# appleii.net
KiCad netlist of a schematic drawn in EAGLE
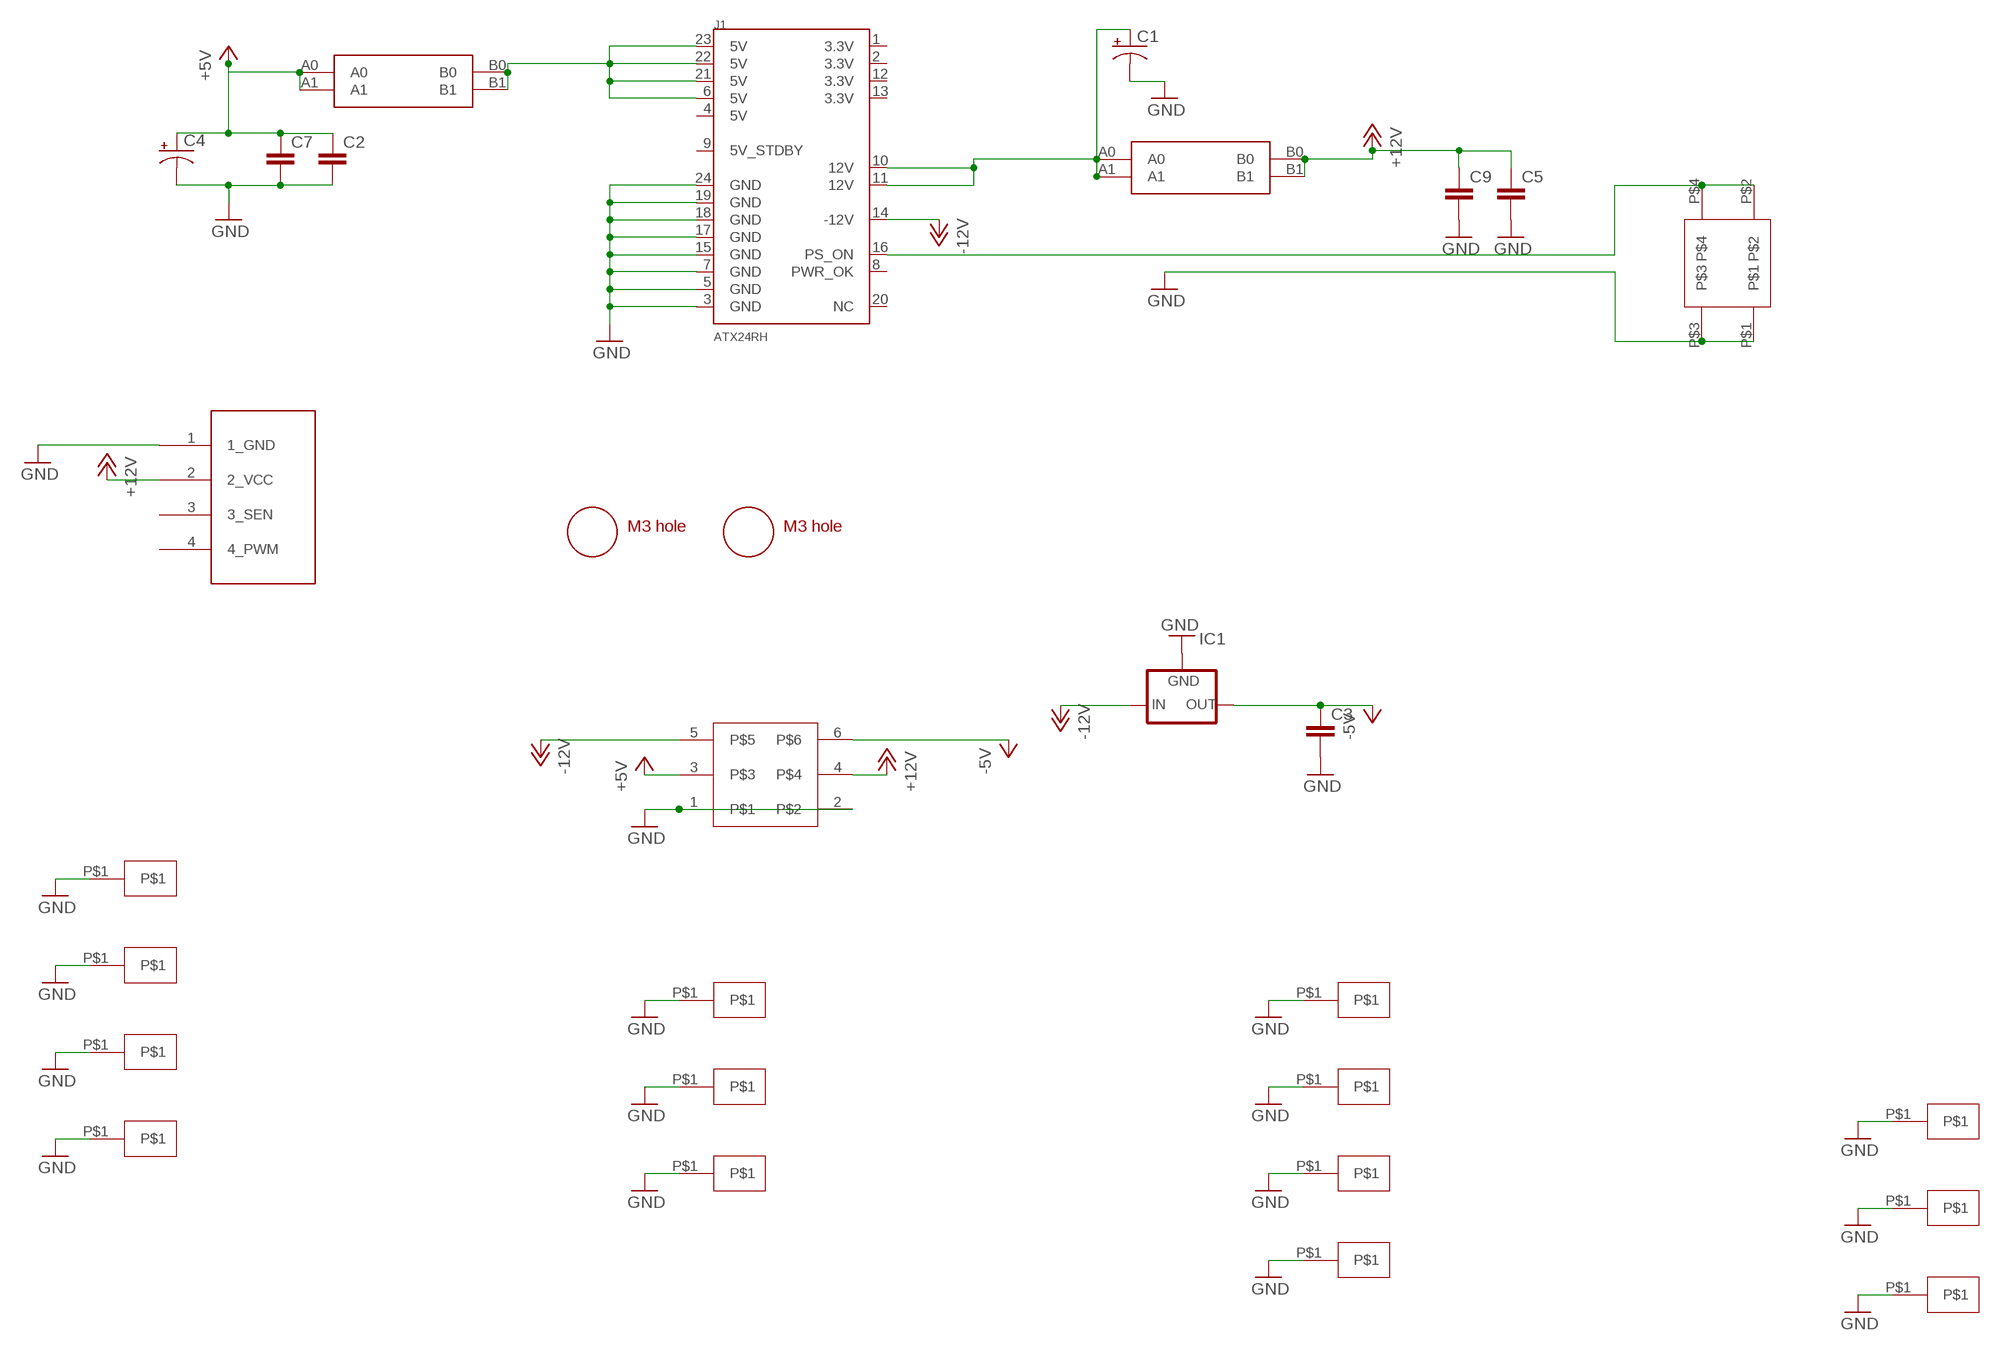
[diagram p0: schematic, sheet 1]

(export (version "E")
  (design (tool "Eeschema 10.0.6"))
  (components
    (comp (ref "C1")
      (value "CPOL-USE3.5-8")
      (footprint "eagle-import:E3,5-8")
      (libsource (lib "eagle-import") (part "CPOL-USE3.5-8"))
    )
    (comp (ref "C2")
      (value "C5/2.5")
      (footprint "eagle-import:C5B2.5")
      (libsource (lib "eagle-import") (part "C5/2.5"))
    )
    (comp (ref "C3")
      (value "C5/2.5")
      (footprint "eagle-import:C5B2.5")
      (libsource (lib "eagle-import") (part "C5/2.5"))
    )
    (comp (ref "C4")
      (value "CPOL-USE3.5-8")
      (footprint "eagle-import:E3,5-8")
      (libsource (lib "eagle-import") (part "CPOL-USE3.5-8"))
    )
    (comp (ref "C5")
      (value "C5/2.5")
      (footprint "eagle-import:C5B2.5")
      (libsource (lib "eagle-import") (part "C5/2.5"))
    )
    (comp (ref "C7")
      (value "C5/2.5")
      (footprint "eagle-import:C5B2.5")
      (libsource (lib "eagle-import") (part "C5/2.5"))
    )
    (comp (ref "C9")
      (value "C5/2.5")
      (footprint "eagle-import:C5B2.5")
      (libsource (lib "eagle-import") (part "C5/2.5"))
    )
    (comp (ref "IC1")
      (value "79XXS")
      (footprint "eagle-import:79XXS")
      (libsource (lib "eagle-import") (part "79XXS"))
    )
    (comp (ref "J1")
      (value "ATX24RH")
      (footprint "eagle-import:ATX24_RIGHT_ANGLE")
      (libsource (lib "eagle-import") (part "ATX24RH"))
    )
    (comp (ref "JP3")
      (value "4PIN_FAN")
      (footprint "eagle-import:1X04")
      (libsource (lib "eagle-import") (part "4PIN_FAN"))
    )
    (comp (ref "U$1")
      (value "CAR_FUSE_HOLDER3IN1")
      (footprint "eagle-import:FUSE_HOLDER_3IN1")
      (libsource (lib "eagle-import") (part "CAR_FUSE_HOLDER3IN1"))
    )
    (comp (ref "U$2")
      (value "CAR_FUSE_HOLDER3IN1")
      (footprint "eagle-import:FUSE_HOLDER_3IN1")
      (libsource (lib "eagle-import") (part "CAR_FUSE_HOLDER3IN1"))
    )
    (comp (ref "U$3")
      (value "ROCK_SW")
      (footprint "eagle-import:ROCK_SWITCH")
      (libsource (lib "eagle-import") (part "ROCK_SW"))
    )
    (comp (ref "U$4")
      (value "M3_MOUNTING_HOLE")
      (footprint "eagle-import:M3_MOUNTING_HOLE_PACK")
      (libsource (lib "eagle-import") (part "M3_MOUNTING_HOLE"))
    )
    (comp (ref "U$5")
      (value "M3_MOUNTING_HOLE")
      (footprint "eagle-import:M3_MOUNTING_HOLE_PACK")
      (libsource (lib "eagle-import") (part "M3_MOUNTING_HOLE"))
    )
    (comp (ref "U$6")
      (value "APPLEII")
      (footprint "eagle-import:APPLEII")
      (libsource (lib "eagle-import") (part "APPLEII"))
    )
    (comp (ref "U$7")
      (value "EDGEPAD")
      (footprint "eagle-import:EDGEPAD")
      (libsource (lib "eagle-import") (part "EDGEPAD"))
    )
    (comp (ref "U$8")
      (value "EDGEPAD")
      (footprint "eagle-import:EDGEPAD")
      (libsource (lib "eagle-import") (part "EDGEPAD"))
    )
    (comp (ref "U$9")
      (value "EDGEPAD")
      (footprint "eagle-import:EDGEPAD")
      (libsource (lib "eagle-import") (part "EDGEPAD"))
    )
    (comp (ref "U$10")
      (value "EDGEPAD")
      (footprint "eagle-import:EDGEPAD")
      (libsource (lib "eagle-import") (part "EDGEPAD"))
    )
    (comp (ref "U$11")
      (value "EDGEPAD")
      (footprint "eagle-import:EDGEPAD")
      (libsource (lib "eagle-import") (part "EDGEPAD"))
    )
    (comp (ref "U$12")
      (value "EDGEPAD")
      (footprint "eagle-import:EDGEPAD")
      (libsource (lib "eagle-import") (part "EDGEPAD"))
    )
    (comp (ref "U$13")
      (value "EDGEPAD")
      (footprint "eagle-import:EDGEPAD")
      (libsource (lib "eagle-import") (part "EDGEPAD"))
    )
    (comp (ref "U$14")
      (value "EDGEPAD")
      (footprint "eagle-import:EDGEPAD")
      (libsource (lib "eagle-import") (part "EDGEPAD"))
    )
    (comp (ref "U$15")
      (value "EDGEPAD")
      (footprint "eagle-import:EDGEPAD")
      (libsource (lib "eagle-import") (part "EDGEPAD"))
    )
    (comp (ref "U$16")
      (value "EDGEPAD")
      (footprint "eagle-import:EDGEPAD")
      (libsource (lib "eagle-import") (part "EDGEPAD"))
    )
    (comp (ref "U$17")
      (value "EDGEPAD")
      (footprint "eagle-import:EDGEPAD")
      (libsource (lib "eagle-import") (part "EDGEPAD"))
    )
    (comp (ref "U$18")
      (value "EDGEPAD")
      (footprint "eagle-import:EDGEPAD")
      (libsource (lib "eagle-import") (part "EDGEPAD"))
    )
    (comp (ref "U$19")
      (value "EDGEPAD")
      (footprint "eagle-import:EDGEPAD")
      (libsource (lib "eagle-import") (part "EDGEPAD"))
    )
    (comp (ref "U$20")
      (value "EDGEPAD")
      (footprint "eagle-import:EDGEPAD")
      (libsource (lib "eagle-import") (part "EDGEPAD"))
    )
  )
  (nets
    (net (code "1") (name "+5V") (class "Default")
      (node (ref "C2") (pin "1") (pinfunction "1_1") (pintype "passive"))
      (node (ref "C4") (pin "+") (pinfunction "+_+") (pintype "passive"))
      (node (ref "C7") (pin "1") (pinfunction "1_1") (pintype "passive"))
      (node (ref "U$1") (pin "A0") (pinfunction "A0_A0") (pintype "bidirectional"))
      (node (ref "U$1") (pin "A1") (pinfunction "A1_A1") (pintype "bidirectional"))
      (node (ref "U$6") (pin "3") (pinfunction "P$3_3") (pintype "bidirectional"))
    )
    (net (code "2") (name "+12V") (class "Default")
      (node (ref "C5") (pin "1") (pinfunction "1_1") (pintype "passive"))
      (node (ref "C9") (pin "1") (pinfunction "1_1") (pintype "passive"))
      (node (ref "JP3") (pin "2") (pinfunction "2_VCC_2") (pintype "passive"))
      (node (ref "U$2") (pin "B0") (pinfunction "B0_B0") (pintype "bidirectional"))
      (node (ref "U$2") (pin "B1") (pinfunction "B1_B1") (pintype "bidirectional"))
      (node (ref "U$6") (pin "4") (pinfunction "P$4_4") (pintype "bidirectional"))
    )
    (net (code "3") (name "-5V") (class "Default")
      (node (ref "C3") (pin "1") (pinfunction "1_1") (pintype "passive"))
      (node (ref "IC1") (pin "OUT") (pinfunction "OUT_OUT") (pintype "passive"))
      (node (ref "U$6") (pin "6") (pinfunction "P$6_6") (pintype "bidirectional"))
    )
    (net (code "4") (name "-12V") (class "Default")
      (node (ref "IC1") (pin "IN") (pinfunction "IN_IN") (pintype "input"))
      (node (ref "J1") (pin "14") (pinfunction "-12V_14") (pintype "bidirectional"))
      (node (ref "U$6") (pin "5") (pinfunction "P$5_5") (pintype "bidirectional"))
    )
    (net (code "5") (name "GND") (class "Default")
      (node (ref "C1") (pin "-") (pinfunction "-_-") (pintype "passive"))
      (node (ref "C2") (pin "2") (pinfunction "2_2") (pintype "passive"))
      (node (ref "C3") (pin "2") (pinfunction "2_2") (pintype "passive"))
      (node (ref "C4") (pin "-") (pinfunction "-_-") (pintype "passive"))
      (node (ref "C5") (pin "2") (pinfunction "2_2") (pintype "passive"))
      (node (ref "C7") (pin "2") (pinfunction "2_2") (pintype "passive"))
      (node (ref "C9") (pin "2") (pinfunction "2_2") (pintype "passive"))
      (node (ref "IC1") (pin "GND") (pinfunction "GND_GND") (pintype "input"))
      (node (ref "J1") (pin "15") (pinfunction "GND_15") (pintype "bidirectional"))
      (node (ref "J1") (pin "17") (pinfunction "GND_17") (pintype "bidirectional"))
      (node (ref "J1") (pin "18") (pinfunction "GND_18") (pintype "bidirectional"))
      (node (ref "J1") (pin "19") (pinfunction "GND_19") (pintype "bidirectional"))
      (node (ref "J1") (pin "24") (pinfunction "GND_24") (pintype "bidirectional"))
      (node (ref "J1") (pin "3") (pinfunction "GND_3") (pintype "bidirectional"))
      (node (ref "J1") (pin "5") (pinfunction "GND_5") (pintype "bidirectional"))
      (node (ref "J1") (pin "7") (pinfunction "GND_7") (pintype "bidirectional"))
      (node (ref "JP3") (pin "1") (pinfunction "1_GND_1") (pintype "passive"))
      (node (ref "U$10") (pin "P$1") (pinfunction "P$1_P$1") (pintype "bidirectional"))
      (node (ref "U$11") (pin "P$1") (pinfunction "P$1_P$1") (pintype "bidirectional"))
      (node (ref "U$12") (pin "P$1") (pinfunction "P$1_P$1") (pintype "bidirectional"))
      (node (ref "U$13") (pin "P$1") (pinfunction "P$1_P$1") (pintype "bidirectional"))
      (node (ref "U$14") (pin "P$1") (pinfunction "P$1_P$1") (pintype "bidirectional"))
      (node (ref "U$15") (pin "P$1") (pinfunction "P$1_P$1") (pintype "bidirectional"))
      (node (ref "U$16") (pin "P$1") (pinfunction "P$1_P$1") (pintype "bidirectional"))
      (node (ref "U$17") (pin "P$1") (pinfunction "P$1_P$1") (pintype "bidirectional"))
      (node (ref "U$18") (pin "P$1") (pinfunction "P$1_P$1") (pintype "bidirectional"))
      (node (ref "U$19") (pin "P$1") (pinfunction "P$1_P$1") (pintype "bidirectional"))
      (node (ref "U$20") (pin "P$1") (pinfunction "P$1_P$1") (pintype "bidirectional"))
      (node (ref "U$3") (pin "P$1") (pinfunction "P$1_P$1") (pintype "bidirectional"))
      (node (ref "U$3") (pin "P$3") (pinfunction "P$3_P$3") (pintype "bidirectional"))
      (node (ref "U$6") (pin "1") (pinfunction "P$1_1") (pintype "bidirectional"))
      (node (ref "U$6") (pin "2") (pinfunction "P$2_2") (pintype "bidirectional"))
      (node (ref "U$7") (pin "P$1") (pinfunction "P$1_P$1") (pintype "bidirectional"))
      (node (ref "U$8") (pin "P$1") (pinfunction "P$1_P$1") (pintype "bidirectional"))
      (node (ref "U$9") (pin "P$1") (pinfunction "P$1_P$1") (pintype "bidirectional"))
    )
    (net (code "6") (name "Net-(C1-Pad+)") (class "Default")
      (node (ref "C1") (pin "+") (pinfunction "+_+") (pintype "passive"))
      (node (ref "J1") (pin "10") (pinfunction "12V_10") (pintype "bidirectional"))
      (node (ref "J1") (pin "11") (pinfunction "12V_11") (pintype "bidirectional"))
      (node (ref "U$2") (pin "A0") (pinfunction "A0_A0") (pintype "bidirectional"))
      (node (ref "U$2") (pin "A1") (pinfunction "A1_A1") (pintype "bidirectional"))
    )
    (net (code "7") (name "Net-(J1-5V-Pad21)") (class "Default")
      (node (ref "J1") (pin "21") (pinfunction "5V_21") (pintype "bidirectional"))
      (node (ref "J1") (pin "22") (pinfunction "5V_22") (pintype "bidirectional"))
      (node (ref "J1") (pin "23") (pinfunction "5V_23") (pintype "bidirectional"))
      (node (ref "J1") (pin "6") (pinfunction "5V_6") (pintype "bidirectional"))
      (node (ref "U$1") (pin "B0") (pinfunction "B0_B0") (pintype "bidirectional"))
      (node (ref "U$1") (pin "B1") (pinfunction "B1_B1") (pintype "bidirectional"))
    )
    (net (code "8") (name "Net-(J1-PS_ON)") (class "Default")
      (node (ref "J1") (pin "16") (pinfunction "PS_ON_16") (pintype "bidirectional"))
      (node (ref "U$3") (pin "P$2") (pinfunction "P$2_P$2") (pintype "bidirectional"))
      (node (ref "U$3") (pin "P$4") (pinfunction "P$4_P$4") (pintype "bidirectional"))
    )
    (net (code "9") (name "unconnected-(J1-3.3V-Pad1)") (class "Default")
      (node (ref "J1") (pin "1") (pinfunction "3.3V_1") (pintype "bidirectional"))
    )
    (net (code "10") (name "unconnected-(J1-3.3V-Pad2)") (class "Default")
      (node (ref "J1") (pin "2") (pinfunction "3.3V_2") (pintype "bidirectional"))
    )
    (net (code "11") (name "unconnected-(J1-3.3V-Pad12)") (class "Default")
      (node (ref "J1") (pin "12") (pinfunction "3.3V_12") (pintype "bidirectional"))
    )
    (net (code "12") (name "unconnected-(J1-3.3V-Pad13)") (class "Default")
      (node (ref "J1") (pin "13") (pinfunction "3.3V_13") (pintype "bidirectional"))
    )
    (net (code "13") (name "unconnected-(J1-5V-Pad4)") (class "Default")
      (node (ref "J1") (pin "4") (pinfunction "5V_4") (pintype "bidirectional"))
    )
    (net (code "14") (name "unconnected-(J1-5V_STDBY-Pad9)") (class "Default")
      (node (ref "J1") (pin "9") (pinfunction "5V_STDBY_9") (pintype "bidirectional"))
    )
    (net (code "15") (name "unconnected-(J1-NC-Pad20)") (class "Default")
      (node (ref "J1") (pin "20") (pinfunction "NC_20") (pintype "bidirectional"))
    )
    (net (code "16") (name "unconnected-(J1-PWR_OK-Pad8)") (class "Default")
      (node (ref "J1") (pin "8") (pinfunction "PWR_OK_8") (pintype "bidirectional"))
    )
    (net (code "17") (name "unconnected-(JP3-3_SEN-Pad3)") (class "Default")
      (node (ref "JP3") (pin "3") (pinfunction "3_SEN_3") (pintype "passive"))
    )
    (net (code "18") (name "unconnected-(JP3-4_PWM-Pad4)") (class "Default")
      (node (ref "JP3") (pin "4") (pinfunction "4_PWM_4") (pintype "passive"))
    )
  )
)
